# Power_Schematic.net
KiCad netlist of a schematic drawn in Altium Designer
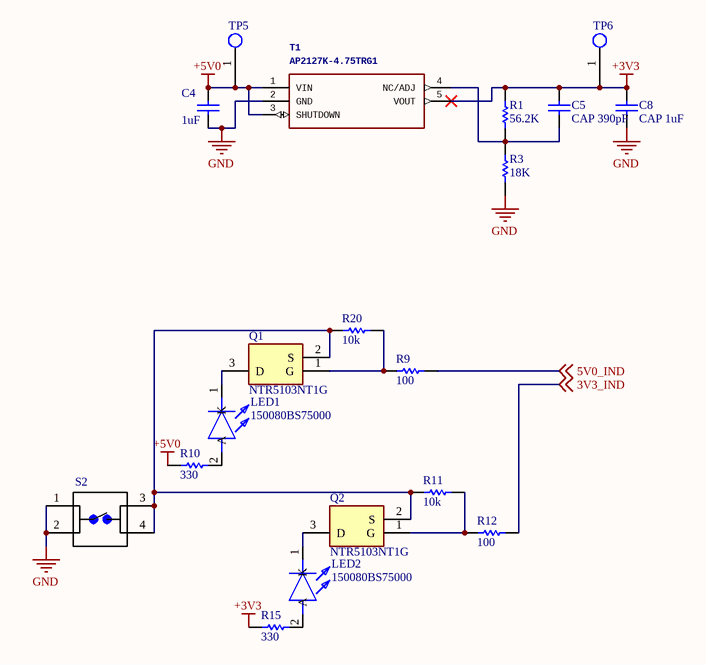
[diagram p0: Power Schematic.SchDoc]

(export (version "E")
  (design (tool "Eeschema 10.0.6"))
  (components
    (comp (ref "C4")
      (value "1uF")
      (footprint "CAPC0805(2012)75_L")
      (description "CAP 2.7pF 50V ±0.1pF 0805 (2012 Metric) Thickness 0.75mm SMD")
      (fields (field (name "TOLERANCE") "Â±0.1pF"))
      (libsource (lib "Integrated_Library - 12.01.19 - 13.05") (part "CMP-1036-00339-1"))
    )
    (comp (ref "C5")
      (value "CAP 390pF")
      (footprint "CAPC0805(2012)75_L")
      (description "CAP 2.7pF 50V ±0.1pF 0805 (2012 Metric) Thickness 0.75mm SMD")
      (fields (field (name "TOLERANCE") "Â±0.1pF"))
      (libsource (lib "Integrated_Library - 12.01.19 - 13.05") (part "CMP-1036-00339-1"))
    )
    (comp (ref "C8")
      (value "CAP 1uF")
      (footprint "CAPC0805(2012)75_L")
      (description "CAP 2.7pF 50V ±0.1pF 0805 (2012 Metric) Thickness 0.75mm SMD")
      (fields (field (name "TOLERANCE") "Â±0.1pF"))
      (libsource (lib "Integrated_Library - 12.01.19 - 13.05") (part "CMP-1036-00339-1"))
    )
    (comp (ref "LED1")
      (value "150080BS75000")
      (footprint "SamacSys:LEDC2012X80N")
      (description "LED")
      (fields
        (field (name "MOUSER PART NUMBER") "710-150080BS75000")
        (field (name "RS PART NUMBER") "8154228P")
      )
      (libsource (lib "*") (part "150080BS75000"))
    )
    (comp (ref "LED2")
      (value "150080BS75000")
      (footprint "SamacSys:LEDC2012X80N")
      (description "LED")
      (fields
        (field (name "MOUSER PART NUMBER") "710-150080BS75000")
        (field (name "RS PART NUMBER") "8154228P")
      )
      (libsource (lib "*") (part "150080BS75000"))
    )
    (comp (ref "Q1")
      (value "NTR5103NT1G")
      (footprint "SamacSys:SOT95P237X101-3N")
      (description "N-MOSFET")
      (fields (field (name "MOUSER PART NUMBER") "863-NTR5103NT1G") (field (name "RS PART NUMBER") "1841331"))
      (libsource (lib "*") (part "NTR5103NT1G"))
    )
    (comp (ref "Q2")
      (value "NTR5103NT1G")
      (footprint "SamacSys:SOT95P237X101-3N")
      (description "N-MOSFET")
      (fields (field (name "MOUSER PART NUMBER") "863-NTR5103NT1G") (field (name "RS PART NUMBER") "1841331"))
      (libsource (lib "*") (part "NTR5103NT1G"))
    )
    (comp (ref "R1")
      (value "56.2K")
      (footprint "RESC2013X70X40LL20T20")
      (description "RES SMD 150K OHM 1% 1/8W 0805")
      (fields (field (name "MANUFACTURER") "Panasonic") (field (name "PART NUMBER") "ERJ-6ENF1503V"))
      (libsource (lib "Altium Content Vault") (part "RES"))
    )
    (comp (ref "R3")
      (value "18K")
      (footprint "RESC2013X70X40LL20T20")
      (description "RES SMD 150K OHM 1% 1/8W 0805")
      (fields (field (name "MANUFACTURER") "Panasonic") (field (name "PART NUMBER") "ERJ-6ENF1503V"))
      (libsource (lib "Altium Content Vault") (part "RES"))
    )
    (comp (ref "R9")
      (value "100")
      (footprint "RESC2013X70X40LL20T20")
      (description "RES SMD 150K OHM 1% 1/8W 0805")
      (fields (field (name "MANUFACTURER") "Panasonic") (field (name "PART NUMBER") "ERJ-6ENF1503V"))
      (libsource (lib "Altium Content Vault") (part "RES"))
    )
    (comp (ref "R10")
      (value "330")
      (footprint "RESC2013X70X40LL20T20")
      (description "RES SMD 150K OHM 1% 1/8W 0805")
      (fields (field (name "MANUFACTURER") "Panasonic") (field (name "PART NUMBER") "ERJ-6ENF1503V"))
      (libsource (lib "Altium Content Vault") (part "RES"))
    )
    (comp (ref "R11")
      (value "10k")
      (footprint "RESC2013X70X40LL20T20")
      (description "RES SMD 150K OHM 1% 1/8W 0805")
      (fields (field (name "MANUFACTURER") "Panasonic") (field (name "PART NUMBER") "ERJ-6ENF1503V"))
      (libsource (lib "Altium Content Vault") (part "RES"))
    )
    (comp (ref "R12")
      (value "100")
      (footprint "RESC2013X70X40LL20T20")
      (description "RES SMD 150K OHM 1% 1/8W 0805")
      (fields (field (name "MANUFACTURER") "Panasonic") (field (name "PART NUMBER") "ERJ-6ENF1503V"))
      (libsource (lib "Altium Content Vault") (part "RES"))
    )
    (comp (ref "R15")
      (value "330")
      (footprint "RESC2013X70X40LL20T20")
      (description "RES SMD 150K OHM 1% 1/8W 0805")
      (fields (field (name "MANUFACTURER") "Panasonic") (field (name "PART NUMBER") "ERJ-6ENF1503V"))
      (libsource (lib "Altium Content Vault") (part "RES"))
    )
    (comp (ref "R20")
      (value "10k")
      (footprint "RESC2013X70X40LL20T20")
      (description "RES SMD 150K OHM 1% 1/8W 0805")
      (fields (field (name "MANUFACTURER") "Panasonic") (field (name "PART NUMBER") "ERJ-6ENF1503V"))
      (libsource (lib "Altium Content Vault") (part "RES"))
    )
    (comp (ref "S2")
      (value "1825910-7")
      (footprint "Switch 6mm 24V (NO)")
      (description "FSM4JAH=6MM TACT SWITCH, HIGH TEMP")
      (fields (field (name "MF") "TE Connectivity") (field (name "DIGI-KEY_PART_NUMBER") "450-1804-ND"))
      (libsource (lib "Husky Robotics Standard Library 2019-2020") (part "Switch 6mm 24V (NO)"))
    )
    (comp (ref "T1")
      (value "AP2127K-4.75TRG1")
      (footprint "SOT95P282X145-5N")
      (description "LDO Voltage Regulators 300mA CMOS LDO 2.5V to 6VSource:  Datasheet")
      (libsource (lib "AP2127K-4") (part "AP2127K-4.75TRG1"))
    )
    (comp (ref "TP5")
      (value "Test Point")
      (footprint "Test Point Through-hole")
      (libsource (lib "Husky Robotics Standard Library 2019-2020") (part "Test Point"))
    )
    (comp (ref "TP6")
      (value "Test Point")
      (footprint "Test Point Through-hole")
      (libsource (lib "Husky Robotics Standard Library 2019-2020") (part "Test Point"))
    )
  )
  (nets
    (net (code "1") (name "+3V3") (class "Default")
      (node (ref "C5") (pin "2") (pinfunction "2_2") (pintype "passive"))
      (node (ref "C8") (pin "2") (pinfunction "2_2") (pintype "passive"))
      (node (ref "R1") (pin "1") (pinfunction "1_1") (pintype "passive"))
      (node (ref "R15") (pin "1") (pinfunction "1_1") (pintype "passive"))
      (node (ref "T1") (pin "5") (pinfunction "VOUT_5") (pintype "output"))
      (node (ref "TP6") (pin "1") (pinfunction "1_1") (pintype "passive"))
    )
    (net (code "2") (name "+5V0") (class "Default")
      (node (ref "C4") (pin "2") (pinfunction "2_2") (pintype "passive"))
      (node (ref "R10") (pin "2") (pinfunction "2_2") (pintype "passive"))
      (node (ref "T1") (pin "1") (pinfunction "VIN_1") (pintype "power_in"))
      (node (ref "T1") (pin "3") (pinfunction "SHUTDOWN_3") (pintype "bidirectional"))
      (node (ref "TP5") (pin "1") (pinfunction "1_1") (pintype "passive"))
    )
    (net (code "3") (name "3V3_IND") (class "Default")
      (node (ref "R12") (pin "1") (pinfunction "1_1") (pintype "passive"))
    )
    (net (code "4") (name "5V0_IND") (class "Default")
      (node (ref "R9") (pin "1") (pinfunction "1_1") (pintype "passive"))
    )
    (net (code "5") (name "GND") (class "Default")
      (node (ref "C4") (pin "1") (pinfunction "1_1") (pintype "passive"))
      (node (ref "C8") (pin "1") (pinfunction "1_1") (pintype "passive"))
      (node (ref "R3") (pin "2") (pinfunction "2_2") (pintype "passive"))
      (node (ref "S2") (pin "1") (pinfunction "1_1") (pintype "passive"))
      (node (ref "S2") (pin "2") (pinfunction "2_2") (pintype "passive"))
      (node (ref "T1") (pin "2") (pinfunction "GND_2") (pintype "power_in"))
    )
    (net (code "6") (name "Net-(LED1-A)") (class "Default")
      (node (ref "LED1") (pin "2") (pinfunction "A_2") (pintype "passive"))
      (node (ref "R10") (pin "1") (pinfunction "1_1") (pintype "passive"))
    )
    (net (code "7") (name "Net-(LED1-K)") (class "Default")
      (node (ref "LED1") (pin "1") (pinfunction "K_1") (pintype "passive"))
      (node (ref "Q1") (pin "3") (pinfunction "D_3") (pintype "passive"))
    )
    (net (code "8") (name "Net-(LED2-A)") (class "Default")
      (node (ref "LED2") (pin "2") (pinfunction "A_2") (pintype "passive"))
      (node (ref "R15") (pin "2") (pinfunction "2_2") (pintype "passive"))
    )
    (net (code "9") (name "Net-(LED2-K)") (class "Default")
      (node (ref "LED2") (pin "1") (pinfunction "K_1") (pintype "passive"))
      (node (ref "Q2") (pin "3") (pinfunction "D_3") (pintype "passive"))
    )
    (net (code "10") (name "Net-(Q1-G)") (class "Default")
      (node (ref "Q1") (pin "1") (pinfunction "G_1") (pintype "passive"))
      (node (ref "R20") (pin "1") (pinfunction "1_1") (pintype "passive"))
      (node (ref "R9") (pin "2") (pinfunction "2_2") (pintype "passive"))
    )
    (net (code "11") (name "Net-(Q1-S)") (class "Default")
      (node (ref "Q1") (pin "2") (pinfunction "S_2") (pintype "passive"))
      (node (ref "Q2") (pin "2") (pinfunction "S_2") (pintype "passive"))
      (node (ref "R11") (pin "2") (pinfunction "2_2") (pintype "passive"))
      (node (ref "R20") (pin "2") (pinfunction "2_2") (pintype "passive"))
      (node (ref "S2") (pin "3") (pinfunction "3_3") (pintype "passive"))
      (node (ref "S2") (pin "4") (pinfunction "4_4") (pintype "passive"))
    )
    (net (code "12") (name "Net-(Q2-G)") (class "Default")
      (node (ref "Q2") (pin "1") (pinfunction "G_1") (pintype "passive"))
      (node (ref "R11") (pin "1") (pinfunction "1_1") (pintype "passive"))
      (node (ref "R12") (pin "2") (pinfunction "2_2") (pintype "passive"))
    )
    (net (code "13") (name "Net-(T1-NC{slash}ADJ)") (class "Default")
      (node (ref "C5") (pin "1") (pinfunction "1_1") (pintype "passive"))
      (node (ref "R1") (pin "2") (pinfunction "2_2") (pintype "passive"))
      (node (ref "R3") (pin "1") (pinfunction "1_1") (pintype "passive"))
      (node (ref "T1") (pin "4") (pinfunction "NC/ADJ_4") (pintype "output"))
    )
  )
)
